# 1_uC.net
KiCad netlist of a schematic drawn in Altium Designer
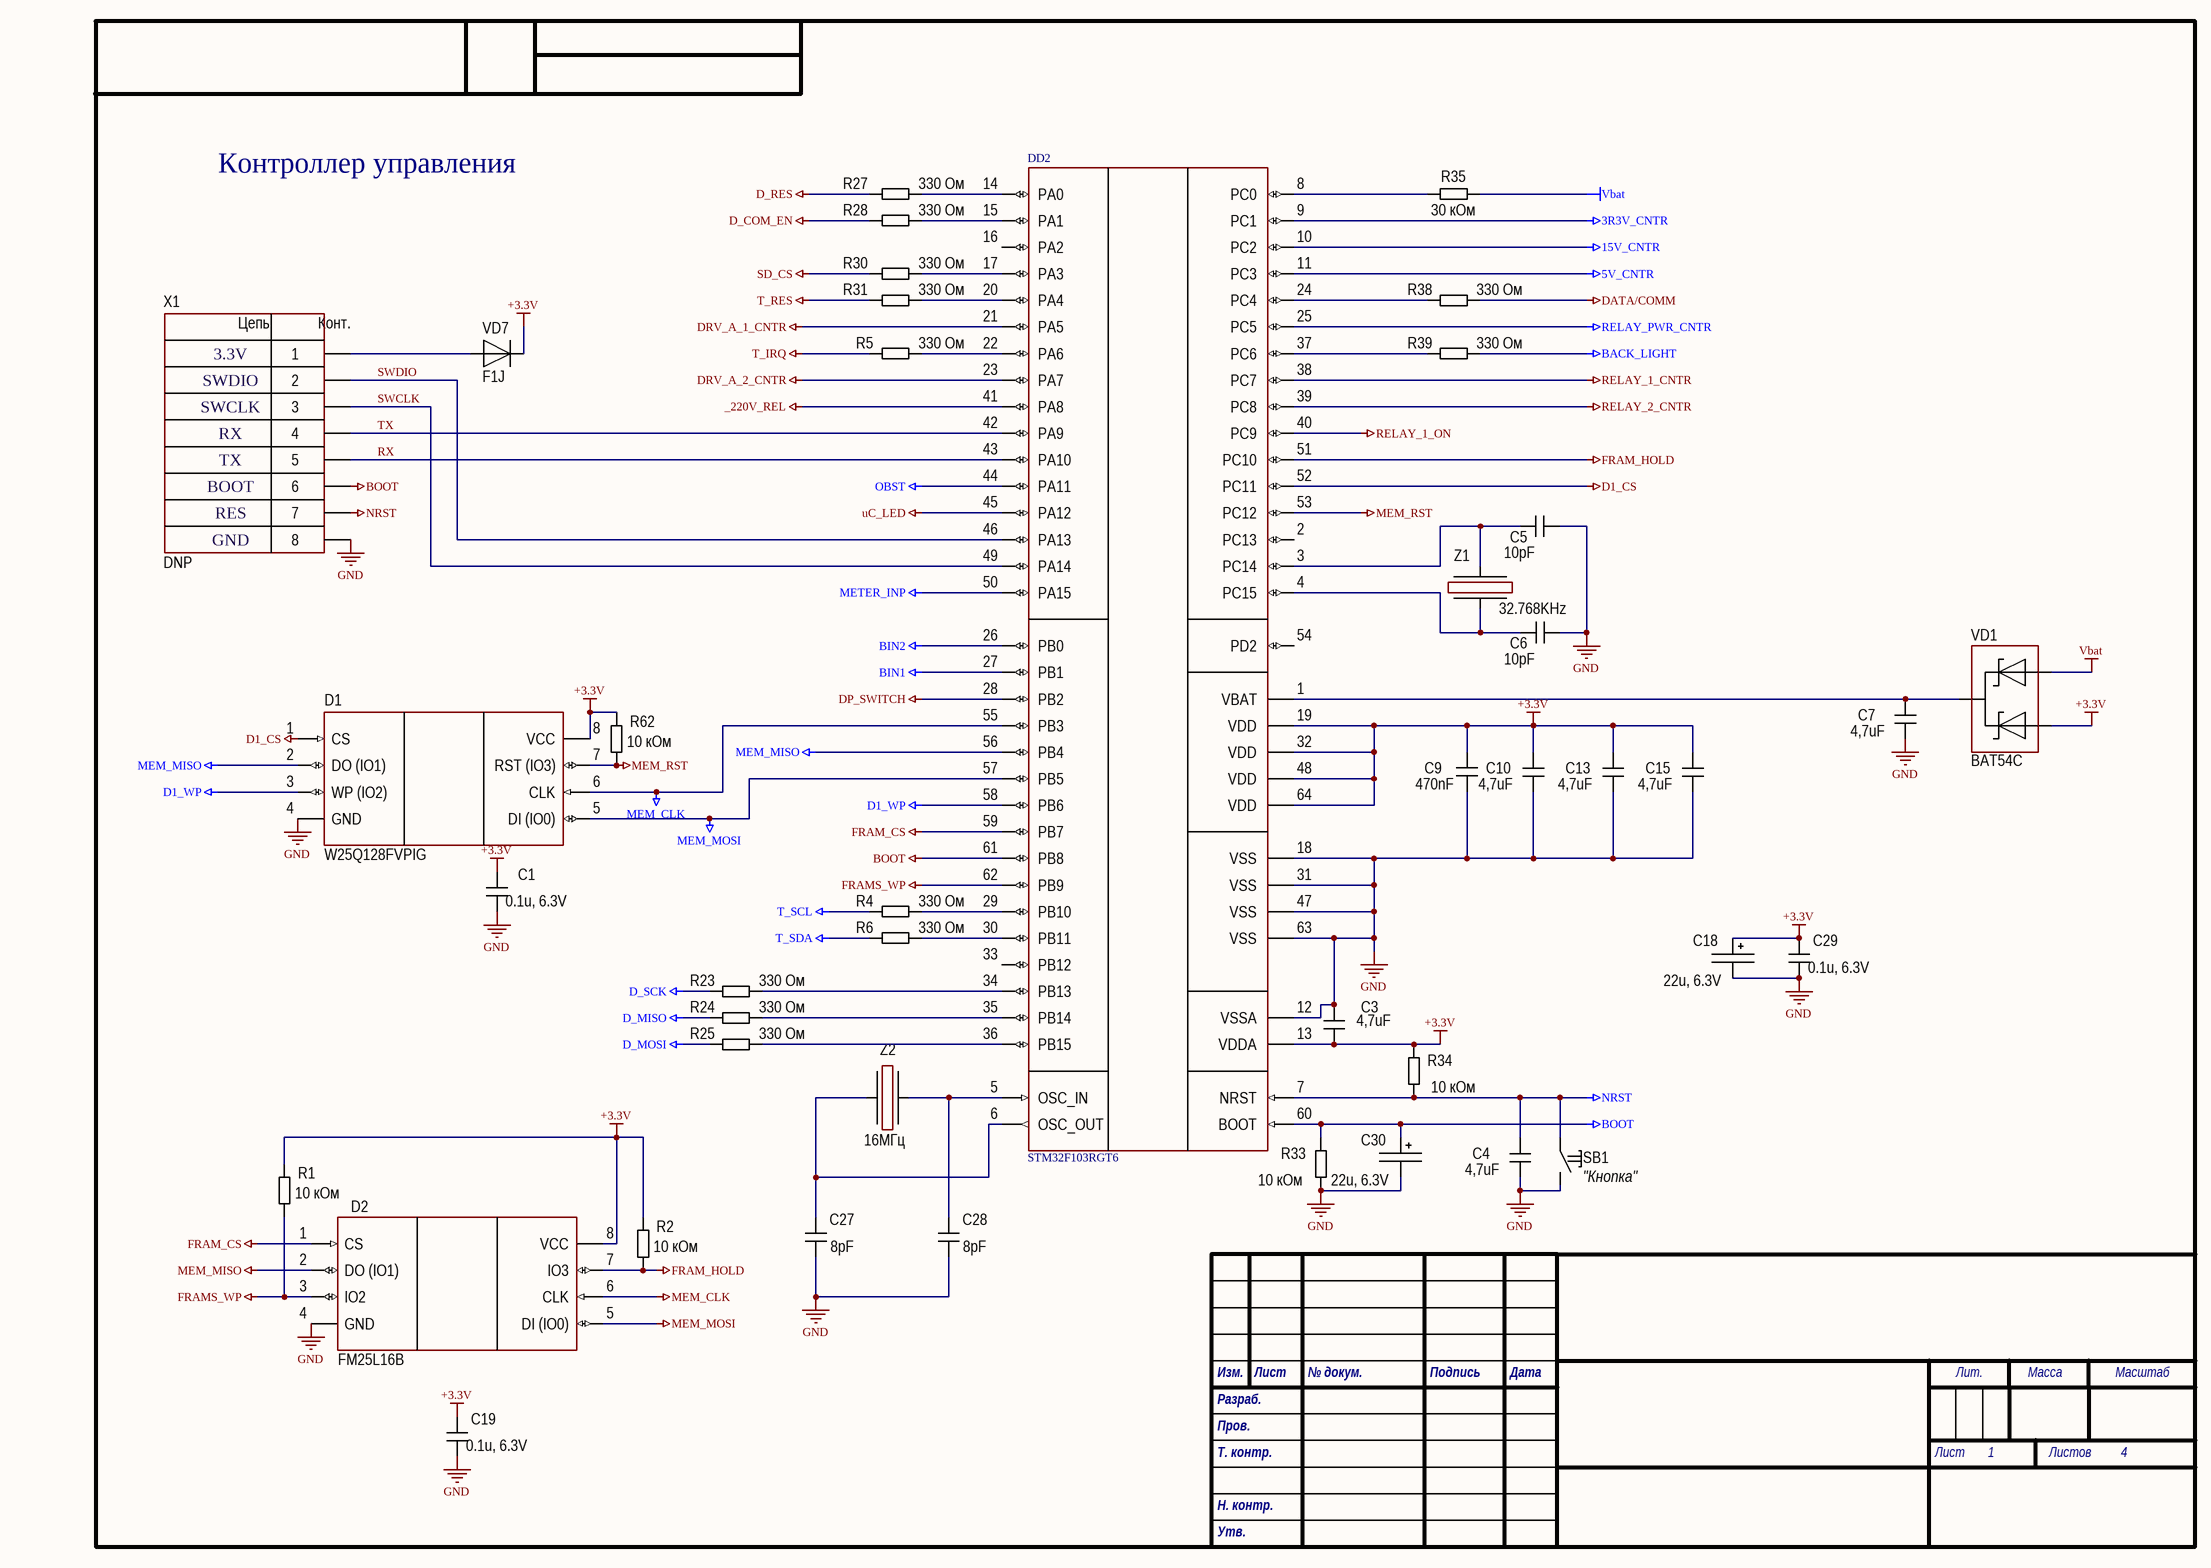
[diagram p0: 1_uC.SchDoc]

(export (version "E")
  (design (tool "Eeschema 10.0.6"))
  (components
    (comp (ref "C1")
      (value "0.1u, 6.3V")
      (footprint "CH0402C")
      (libsource (lib "Condensators") (part "Capacitor"))
    )
    (comp (ref "C3")
      (value "4,7uF")
      (footprint "CH0402C")
      (description "0402")
      (libsource (lib "Condensators") (part "Capacitor"))
    )
    (comp (ref "C4")
      (value "4,7uF")
      (footprint "CH0402C")
      (description "0402")
      (libsource (lib "Condensators") (part "Capacitor"))
    )
    (comp (ref "C5")
      (value "10pF")
      (footprint "CH0402C")
      (description "0402")
      (libsource (lib "Condensators") (part "Capacitor"))
    )
    (comp (ref "C6")
      (value "10pF")
      (footprint "CH0402C")
      (description "0402")
      (libsource (lib "Condensators") (part "Capacitor"))
    )
    (comp (ref "C7")
      (value "4,7uF")
      (footprint "CH0402C")
      (description "0402")
      (libsource (lib "Condensators") (part "Capacitor"))
    )
    (comp (ref "C9")
      (value "470nF")
      (footprint "CH0402C")
      (description "0402")
      (libsource (lib "Condensators") (part "Capacitor"))
    )
    (comp (ref "C10")
      (value "4,7uF")
      (footprint "CH0402C")
      (description "0402")
      (libsource (lib "Condensators") (part "Capacitor"))
    )
    (comp (ref "C13")
      (value "4,7uF")
      (footprint "CH0402C")
      (description "0402")
      (libsource (lib "Condensators") (part "Capacitor"))
    )
    (comp (ref "C15")
      (value "4,7uF")
      (footprint "CH0402C")
      (description "0402")
      (libsource (lib "Condensators") (part "Capacitor"))
    )
    (comp (ref "C18")
      (value "22u, 6.3V")
      (footprint "TANTAL_A")
      (libsource (lib "Condensators") (part "TantalCap"))
    )
    (comp (ref "C19")
      (value "0.1u, 6.3V")
      (footprint "CH0402C")
      (libsource (lib "Condensators") (part "Capacitor"))
    )
    (comp (ref "C27")
      (value "8pF")
      (footprint "CH0402C")
      (description "0402")
      (libsource (lib "Condensators") (part "Capacitor"))
    )
    (comp (ref "C28")
      (value "8pF")
      (footprint "CH0402C")
      (description "0402")
      (libsource (lib "Condensators") (part "Capacitor"))
    )
    (comp (ref "C29")
      (value "0.1u, 6.3V")
      (footprint "CH0402C")
      (libsource (lib "Condensators") (part "Capacitor"))
    )
    (comp (ref "C30")
      (value "22u, 6.3V")
      (footprint "TANTAL_A")
      (libsource (lib "Condensators") (part "TantalCap"))
    )
    (comp (ref "D1")
      (value "W25Q128FVPIG")
      (footprint "8-WSON (5x6mm)without_holes")
      (description "Flash")
      (fields (field (name "MANUFACTURER") "Winbond Electronics"))
      (libsource (lib "MicroIC") (part "W25Q128FVPIG"))
    )
    (comp (ref "D2")
      (value "FM25L16B")
      (footprint "8-SOIC")
      (description "Flash")
      (fields (field (name "MANUFACTURER") "Winbond Electronics"))
      (libsource (lib "MicroIC") (part "W25Q80JVSSIQ"))
    )
    (comp (ref "DD2")
      (value "STM32F103RGT6")
      (footprint "64-LQFP")
      (description "Cortex-M3 (64-LQFP)")
      (libsource (lib "MicroIC") (part "STM32F103RCT6"))
    )
    (comp (ref "R1")
      (value "10 кОм")
      (footprint "CH0402R")
      (description "0603")
      (libsource (lib "Resistors") (part "Resistor"))
    )
    (comp (ref "R2")
      (value "10 кОм")
      (footprint "CH0402R")
      (description "0603")
      (libsource (lib "Resistors") (part "Resistor"))
    )
    (comp (ref "R4")
      (value "330 Ом")
      (footprint "CH0402R")
      (description "0603")
      (libsource (lib "Resistors") (part "Resistor"))
    )
    (comp (ref "R5")
      (value "330 Ом")
      (footprint "CH0402R")
      (description "0603")
      (libsource (lib "Resistors") (part "Resistor"))
    )
    (comp (ref "R6")
      (value "330 Ом")
      (footprint "CH0402R")
      (description "0603")
      (libsource (lib "Resistors") (part "Resistor"))
    )
    (comp (ref "R23")
      (value "330 Ом")
      (footprint "CH0402R")
      (description "0603")
      (libsource (lib "Resistors") (part "Resistor"))
    )
    (comp (ref "R24")
      (value "330 Ом")
      (footprint "CH0402R")
      (description "0603")
      (libsource (lib "Resistors") (part "Resistor"))
    )
    (comp (ref "R25")
      (value "330 Ом")
      (footprint "CH0402R")
      (description "0603")
      (libsource (lib "Resistors") (part "Resistor"))
    )
    (comp (ref "R27")
      (value "330 Ом")
      (footprint "CH0402R")
      (description "0603")
      (libsource (lib "Resistors") (part "Resistor"))
    )
    (comp (ref "R28")
      (value "330 Ом")
      (footprint "CH0402R")
      (description "0603")
      (libsource (lib "Resistors") (part "Resistor"))
    )
    (comp (ref "R30")
      (value "330 Ом")
      (footprint "CH0402R")
      (description "0603")
      (libsource (lib "Resistors") (part "Resistor"))
    )
    (comp (ref "R31")
      (value "330 Ом")
      (footprint "CH0402R")
      (description "0603")
      (libsource (lib "Resistors") (part "Resistor"))
    )
    (comp (ref "R33")
      (value "10 кОм")
      (footprint "CH0402R")
      (description "0805")
      (libsource (lib "Resistors") (part "Resistor"))
    )
    (comp (ref "R34")
      (value "10 кОм")
      (footprint "CH0402R")
      (description "0805")
      (libsource (lib "Resistors") (part "Resistor"))
    )
    (comp (ref "R35")
      (value "30 кОм")
      (footprint "CH0402R")
      (description "0603")
      (libsource (lib "Resistors") (part "Resistor"))
    )
    (comp (ref "R38")
      (value "330 Ом")
      (footprint "CH0402R")
      (description "0603")
      (libsource (lib "Resistors") (part "Resistor"))
    )
    (comp (ref "R39")
      (value "330 Ом")
      (footprint "CH0402R")
      (description "0603")
      (libsource (lib "Resistors") (part "Resistor"))
    )
    (comp (ref "R62")
      (value "10 кОм")
      (footprint "CH0402R")
      (description "0603")
      (libsource (lib "Resistors") (part "Resistor"))
    )
    (comp (ref "SB1")
      (value "\"Кнопка\"")
      (footprint "TL1014BF160QG")
      (description "6x6 mm")
      (libsource (lib "Connectors") (part "Tactile switches"))
    )
    (comp (ref "VD1")
      (value "BAT54C")
      (footprint "SOT23_123")
      (description "SOT-23")
      (libsource (lib "Diods") (part "Diod Schottky Array v.1"))
    )
    (comp (ref "VD7") (value "F1J") (footprint "SOD123F") (libsource (lib "Diods") (part "Diod")))
    (comp (ref "X1")
      (value "DNP")
      (footprint "CON: PBS-8")
      (description "Pin header 8")
      (libsource (lib "Connectors") (part "8-Connector"))
    )
    (comp (ref "Z1")
      (value "32.768KHz")
      (footprint "OSC: 3215")
      (libsource (lib "Melochi") (part "Oscillator"))
    )
    (comp (ref "Z2")
      (value "16МГц")
      (footprint "OSC: ABM3")
      (description "NX5032GA-16.000000MHZ-LN-CD-1")
      (libsource (lib "") (part "Oscillator_1"))
    )
  )
  (nets
    (net (code "1") (name "+3.3V") (class "Default")
      (node (ref "C1") (pin "2") (pinfunction "2_2") (pintype "passive"))
      (node (ref "C10") (pin "2") (pinfunction "2_2") (pintype "passive"))
      (node (ref "C13") (pin "2") (pinfunction "2_2") (pintype "passive"))
      (node (ref "C15") (pin "2") (pinfunction "2_2") (pintype "passive"))
      (node (ref "C18") (pin "1") (pinfunction "1_1") (pintype "power_in"))
      (node (ref "C19") (pin "2") (pinfunction "2_2") (pintype "passive"))
      (node (ref "C29") (pin "2") (pinfunction "2_2") (pintype "passive"))
      (node (ref "C3") (pin "1") (pinfunction "1_1") (pintype "passive"))
      (node (ref "C9") (pin "1") (pinfunction "1_1") (pintype "passive"))
      (node (ref "D1") (pin "8") (pinfunction "VCC_8") (pintype "power_in"))
      (node (ref "D2") (pin "8") (pinfunction "VCC_8") (pintype "power_in"))
      (node (ref "DD2") (pin "13") (pinfunction "VDDA_13") (pintype "power_in"))
      (node (ref "DD2") (pin "19") (pinfunction "VDD_19") (pintype "power_in"))
      (node (ref "DD2") (pin "32") (pinfunction "VDD_32") (pintype "power_in"))
      (node (ref "DD2") (pin "48") (pinfunction "VDD_48") (pintype "power_in"))
      (node (ref "DD2") (pin "64") (pinfunction "VDD_64") (pintype "power_in"))
      (node (ref "R1") (pin "2") (pinfunction "2_2") (pintype "passive"))
      (node (ref "R2") (pin "2") (pinfunction "2_2") (pintype "passive"))
      (node (ref "R34") (pin "2") (pinfunction "2_2") (pintype "passive"))
      (node (ref "R62") (pin "2") (pinfunction "2_2") (pintype "passive"))
      (node (ref "VD1") (pin "3") (pinfunction "3_3") (pintype "passive"))
      (node (ref "VD7") (pin "2") (pinfunction "2_2") (pintype "passive"))
    )
    (net (code "2") (name "/RX") (class "Default")
      (node (ref "DD2") (pin "43") (pinfunction "PA10_43") (pintype "bidirectional"))
      (node (ref "X1") (pin "5") (pinfunction "5_5") (pintype "power_in"))
    )
    (net (code "3") (name "/SWCLK") (class "Default")
      (node (ref "DD2") (pin "49") (pinfunction "PA14_49") (pintype "bidirectional"))
      (node (ref "X1") (pin "3") (pinfunction "3_3") (pintype "power_in"))
    )
    (net (code "4") (name "/SWDIO") (class "Default")
      (node (ref "DD2") (pin "46") (pinfunction "PA13_46") (pintype "bidirectional"))
      (node (ref "X1") (pin "2") (pinfunction "2_2") (pintype "passive"))
    )
    (net (code "5") (name "/TX") (class "Default")
      (node (ref "DD2") (pin "42") (pinfunction "PA9_42") (pintype "bidirectional"))
      (node (ref "X1") (pin "4") (pinfunction "4_4") (pintype "power_in"))
    )
    (net (code "6") (name "3R3V_CNTR") (class "Default")
      (node (ref "DD2") (pin "9") (pinfunction "PC1_9") (pintype "bidirectional"))
    )
    (net (code "7") (name "5V_CNTR") (class "Default")
      (node (ref "DD2") (pin "11") (pinfunction "PC3_11") (pintype "bidirectional"))
    )
    (net (code "8") (name "15V_CNTR") (class "Default")
      (node (ref "DD2") (pin "10") (pinfunction "PC2_10") (pintype "bidirectional"))
    )
    (net (code "9") (name "BACK_LIGHT") (class "Default")
      (node (ref "R39") (pin "1") (pinfunction "1_1") (pintype "passive"))
    )
    (net (code "10") (name "BIN1") (class "Default")
      (node (ref "DD2") (pin "27") (pinfunction "PB1_27") (pintype "bidirectional"))
    )
    (net (code "11") (name "BIN2") (class "Default")
      (node (ref "DD2") (pin "26") (pinfunction "PB0_26") (pintype "bidirectional"))
    )
    (net (code "12") (name "BOOT") (class "Default")
      (node (ref "C30") (pin "1") (pinfunction "1_1") (pintype "power_in"))
      (node (ref "DD2") (pin "60") (pinfunction "BOOT_60") (pintype "input"))
      (node (ref "DD2") (pin "61") (pinfunction "PB8_61") (pintype "bidirectional"))
      (node (ref "R33") (pin "2") (pinfunction "2_2") (pintype "passive"))
      (node (ref "X1") (pin "6") (pinfunction "6_6") (pintype "power_in"))
    )
    (net (code "13") (name "D1_CS") (class "Default")
      (node (ref "D1") (pin "1") (pinfunction "CS_1") (pintype "input"))
      (node (ref "DD2") (pin "52") (pinfunction "PC11_52") (pintype "bidirectional"))
    )
    (net (code "14") (name "D1_WP") (class "Default")
      (node (ref "D1") (pin "3") (pinfunction "WP_(IO2)_3") (pintype "bidirectional"))
      (node (ref "DD2") (pin "58") (pinfunction "PB6_58") (pintype "bidirectional"))
    )
    (net (code "15") (name "DATA{slash}COMM") (class "Default")
      (node (ref "R38") (pin "1") (pinfunction "1_1") (pintype "passive"))
    )
    (net (code "16") (name "DP_SWITCH") (class "Default")
      (node (ref "DD2") (pin "28") (pinfunction "PB2_28") (pintype "bidirectional"))
    )
    (net (code "17") (name "DRV_A_1_CNTR") (class "Default")
      (node (ref "DD2") (pin "21") (pinfunction "PA5_21") (pintype "bidirectional"))
    )
    (net (code "18") (name "DRV_A_2_CNTR") (class "Default")
      (node (ref "DD2") (pin "23") (pinfunction "PA7_23") (pintype "bidirectional"))
    )
    (net (code "19") (name "D_COM_EN") (class "Default")
      (node (ref "R28") (pin "1") (pinfunction "1_1") (pintype "passive"))
    )
    (net (code "20") (name "D_MISO") (class "Default")
      (node (ref "R24") (pin "1") (pinfunction "1_1") (pintype "passive"))
    )
    (net (code "21") (name "D_MOSI") (class "Default")
      (node (ref "R25") (pin "1") (pinfunction "1_1") (pintype "passive"))
    )
    (net (code "22") (name "D_RES") (class "Default")
      (node (ref "R27") (pin "1") (pinfunction "1_1") (pintype "passive"))
    )
    (net (code "23") (name "D_SCK") (class "Default")
      (node (ref "R23") (pin "1") (pinfunction "1_1") (pintype "passive"))
    )
    (net (code "24") (name "FRAMS_WP") (class "Default")
      (node (ref "D2") (pin "3") (pinfunction "IO2_3") (pintype "bidirectional"))
      (node (ref "DD2") (pin "62") (pinfunction "PB9_62") (pintype "bidirectional"))
      (node (ref "R1") (pin "1") (pinfunction "1_1") (pintype "passive"))
    )
    (net (code "25") (name "FRAM_CS") (class "Default")
      (node (ref "D2") (pin "1") (pinfunction "CS_1") (pintype "input"))
      (node (ref "DD2") (pin "59") (pinfunction "PB7_59") (pintype "bidirectional"))
    )
    (net (code "26") (name "FRAM_HOLD") (class "Default")
      (node (ref "D2") (pin "7") (pinfunction "IO3_7") (pintype "bidirectional"))
      (node (ref "DD2") (pin "51") (pinfunction "PC10_51") (pintype "bidirectional"))
      (node (ref "R2") (pin "1") (pinfunction "1_1") (pintype "passive"))
    )
    (net (code "27") (name "GND") (class "Default")
      (node (ref "C1") (pin "1") (pinfunction "1_1") (pintype "passive"))
      (node (ref "C10") (pin "1") (pinfunction "1_1") (pintype "passive"))
      (node (ref "C13") (pin "1") (pinfunction "1_1") (pintype "passive"))
      (node (ref "C15") (pin "1") (pinfunction "1_1") (pintype "passive"))
      (node (ref "C18") (pin "2") (pinfunction "2_2") (pintype "power_in"))
      (node (ref "C19") (pin "1") (pinfunction "1_1") (pintype "passive"))
      (node (ref "C27") (pin "1") (pinfunction "1_1") (pintype "passive"))
      (node (ref "C28") (pin "1") (pinfunction "1_1") (pintype "passive"))
      (node (ref "C29") (pin "1") (pinfunction "1_1") (pintype "passive"))
      (node (ref "C3") (pin "2") (pinfunction "2_2") (pintype "passive"))
      (node (ref "C30") (pin "2") (pinfunction "2_2") (pintype "power_in"))
      (node (ref "C4") (pin "1") (pinfunction "1_1") (pintype "passive"))
      (node (ref "C5") (pin "2") (pinfunction "2_2") (pintype "passive"))
      (node (ref "C6") (pin "1") (pinfunction "1_1") (pintype "passive"))
      (node (ref "C7") (pin "1") (pinfunction "1_1") (pintype "passive"))
      (node (ref "C9") (pin "2") (pinfunction "2_2") (pintype "passive"))
      (node (ref "D1") (pin "4") (pinfunction "GND_4") (pintype "power_in"))
      (node (ref "D2") (pin "4") (pinfunction "GND_4") (pintype "power_in"))
      (node (ref "DD2") (pin "12") (pinfunction "VSSA_12") (pintype "power_in"))
      (node (ref "DD2") (pin "18") (pinfunction "VSS_18") (pintype "power_in"))
      (node (ref "DD2") (pin "31") (pinfunction "VSS_31") (pintype "power_in"))
      (node (ref "DD2") (pin "47") (pinfunction "VSS_47") (pintype "power_in"))
      (node (ref "DD2") (pin "63") (pinfunction "VSS_63") (pintype "power_in"))
      (node (ref "R33") (pin "1") (pinfunction "1_1") (pintype "passive"))
      (node (ref "SB1") (pin "2") (pinfunction "2_2") (pintype "passive"))
      (node (ref "X1") (pin "8") (pinfunction "8_8") (pintype "power_in"))
    )
    (net (code "28") (name "MEM_CLK") (class "Default")
      (node (ref "D1") (pin "6") (pinfunction "CLK_6") (pintype "input"))
      (node (ref "D2") (pin "6") (pinfunction "CLK_6") (pintype "input"))
      (node (ref "DD2") (pin "55") (pinfunction "PB3_55") (pintype "bidirectional"))
    )
    (net (code "29") (name "MEM_MISO") (class "Default")
      (node (ref "D1") (pin "2") (pinfunction "DO_(IO1)_2") (pintype "bidirectional"))
      (node (ref "D2") (pin "2") (pinfunction "DO_(IO1)_2") (pintype "bidirectional"))
      (node (ref "DD2") (pin "56") (pinfunction "PB4_56") (pintype "bidirectional"))
    )
    (net (code "30") (name "MEM_MOSI") (class "Default")
      (node (ref "D1") (pin "5") (pinfunction "DI_(IO0)_5") (pintype "bidirectional"))
      (node (ref "D2") (pin "5") (pinfunction "DI_(IO0)_5") (pintype "bidirectional"))
      (node (ref "DD2") (pin "57") (pinfunction "PB5_57") (pintype "bidirectional"))
    )
    (net (code "31") (name "MEM_RST") (class "Default")
      (node (ref "D1") (pin "7") (pinfunction "RST_(IO3)_7") (pintype "bidirectional"))
      (node (ref "DD2") (pin "53") (pinfunction "PC12_53") (pintype "bidirectional"))
      (node (ref "R62") (pin "1") (pinfunction "1_1") (pintype "passive"))
    )
    (net (code "32") (name "METER_INP") (class "Default")
      (node (ref "DD2") (pin "50") (pinfunction "PA15_50") (pintype "bidirectional"))
    )
    (net (code "33") (name "NRST") (class "Default")
      (node (ref "C4") (pin "2") (pinfunction "2_2") (pintype "passive"))
      (node (ref "DD2") (pin "7") (pinfunction "NRST_7") (pintype "input"))
      (node (ref "R34") (pin "1") (pinfunction "1_1") (pintype "passive"))
      (node (ref "SB1") (pin "1") (pinfunction "1_1") (pintype "passive"))
      (node (ref "X1") (pin "7") (pinfunction "7_7") (pintype "power_in"))
    )
    (net (code "34") (name "Net-(DD2-OSC_IN)") (class "Default")
      (node (ref "C28") (pin "2") (pinfunction "2_2") (pintype "passive"))
      (node (ref "DD2") (pin "5") (pinfunction "OSC_IN_5") (pintype "input"))
      (node (ref "Z2") (pin "3") (pinfunction "3_3") (pintype "passive"))
    )
    (net (code "35") (name "Net-(DD2-OSC_OUT)") (class "Default")
      (node (ref "C27") (pin "2") (pinfunction "2_2") (pintype "passive"))
      (node (ref "DD2") (pin "6") (pinfunction "OSC_OUT_6") (pintype "output"))
      (node (ref "Z2") (pin "1") (pinfunction "1_1") (pintype "passive"))
    )
    (net (code "36") (name "Net-(DD2-PA0)") (class "Default")
      (node (ref "DD2") (pin "14") (pinfunction "PA0_14") (pintype "bidirectional"))
      (node (ref "R27") (pin "2") (pinfunction "2_2") (pintype "passive"))
    )
    (net (code "37") (name "Net-(DD2-PA1)") (class "Default")
      (node (ref "DD2") (pin "15") (pinfunction "PA1_15") (pintype "bidirectional"))
      (node (ref "R28") (pin "2") (pinfunction "2_2") (pintype "passive"))
    )
    (net (code "38") (name "Net-(DD2-PA3)") (class "Default")
      (node (ref "DD2") (pin "17") (pinfunction "PA3_17") (pintype "bidirectional"))
      (node (ref "R30") (pin "2") (pinfunction "2_2") (pintype "passive"))
    )
    (net (code "39") (name "Net-(DD2-PA4)") (class "Default")
      (node (ref "DD2") (pin "20") (pinfunction "PA4_20") (pintype "bidirectional"))
      (node (ref "R31") (pin "2") (pinfunction "2_2") (pintype "passive"))
    )
    (net (code "40") (name "Net-(DD2-PA6)") (class "Default")
      (node (ref "DD2") (pin "22") (pinfunction "PA6_22") (pintype "bidirectional"))
      (node (ref "R5") (pin "2") (pinfunction "2_2") (pintype "passive"))
    )
    (net (code "41") (name "Net-(DD2-PB10)") (class "Default")
      (node (ref "DD2") (pin "29") (pinfunction "PB10_29") (pintype "bidirectional"))
      (node (ref "R4") (pin "2") (pinfunction "2_2") (pintype "passive"))
    )
    (net (code "42") (name "Net-(DD2-PB11)") (class "Default")
      (node (ref "DD2") (pin "30") (pinfunction "PB11_30") (pintype "bidirectional"))
      (node (ref "R6") (pin "2") (pinfunction "2_2") (pintype "passive"))
    )
    (net (code "43") (name "Net-(DD2-PB13)") (class "Default")
      (node (ref "DD2") (pin "34") (pinfunction "PB13_34") (pintype "bidirectional"))
      (node (ref "R23") (pin "2") (pinfunction "2_2") (pintype "passive"))
    )
    (net (code "44") (name "Net-(DD2-PB14)") (class "Default")
      (node (ref "DD2") (pin "35") (pinfunction "PB14_35") (pintype "bidirectional"))
      (node (ref "R24") (pin "2") (pinfunction "2_2") (pintype "passive"))
    )
    (net (code "45") (name "Net-(DD2-PB15)") (class "Default")
      (node (ref "DD2") (pin "36") (pinfunction "PB15_36") (pintype "bidirectional"))
      (node (ref "R25") (pin "2") (pinfunction "2_2") (pintype "passive"))
    )
    (net (code "46") (name "Net-(DD2-PC0)") (class "Default")
      (node (ref "DD2") (pin "8") (pinfunction "PC0_8") (pintype "bidirectional"))
      (node (ref "R35") (pin "2") (pinfunction "2_2") (pintype "passive"))
    )
    (net (code "47") (name "Net-(DD2-PC4)") (class "Default")
      (node (ref "DD2") (pin "24") (pinfunction "PC4_24") (pintype "bidirectional"))
      (node (ref "R38") (pin "2") (pinfunction "2_2") (pintype "passive"))
    )
    (net (code "48") (name "Net-(DD2-PC6)") (class "Default")
      (node (ref "DD2") (pin "37") (pinfunction "PC6_37") (pintype "bidirectional"))
      (node (ref "R39") (pin "2") (pinfunction "2_2") (pintype "passive"))
    )
    (net (code "49") (name "Net-(DD2-PC14)") (class "Default")
      (node (ref "C5") (pin "1") (pinfunction "1_1") (pintype "passive"))
      (node (ref "DD2") (pin "3") (pinfunction "PC14_3") (pintype "bidirectional"))
      (node (ref "Z1") (pin "3") (pinfunction "3_3") (pintype "passive"))
    )
    (net (code "50") (name "Net-(DD2-PC15)") (class "Default")
      (node (ref "C6") (pin "2") (pinfunction "2_2") (pintype "passive"))
      (node (ref "DD2") (pin "4") (pinfunction "PC15_4") (pintype "bidirectional"))
      (node (ref "Z1") (pin "1") (pinfunction "1_1") (pintype "passive"))
    )
    (net (code "51") (name "Net-(DD2-VBAT)") (class "Default")
      (node (ref "C7") (pin "2") (pinfunction "2_2") (pintype "passive"))
      (node (ref "DD2") (pin "1") (pinfunction "VBAT_1") (pintype "power_in"))
      (node (ref "VD1") (pin "2") (pinfunction "2_2") (pintype "passive"))
    )
    (net (code "52") (name "Net-(VD7-Pad1)") (class "Default")
      (node (ref "VD7") (pin "1") (pinfunction "1_1") (pintype "passive"))
      (node (ref "X1") (pin "1") (pinfunction "1_1") (pintype "passive"))
    )
    (net (code "53") (name "OBST") (class "Default")
      (node (ref "DD2") (pin "44") (pinfunction "PA11_44") (pintype "bidirectional"))
    )
    (net (code "54") (name "RELAY_1_CNTR") (class "Default")
      (node (ref "DD2") (pin "38") (pinfunction "PC7_38") (pintype "bidirectional"))
    )
    (net (code "55") (name "RELAY_1_ON") (class "Default")
      (node (ref "DD2") (pin "40") (pinfunction "PC9_40") (pintype "bidirectional"))
    )
    (net (code "56") (name "RELAY_2_CNTR") (class "Default")
      (node (ref "DD2") (pin "39") (pinfunction "PC8_39") (pintype "bidirectional"))
    )
    (net (code "57") (name "RELAY_PWR_CNTR") (class "Default")
      (node (ref "DD2") (pin "25") (pinfunction "PC5_25") (pintype "bidirectional"))
    )
    (net (code "58") (name "SD_CS") (class "Default")
      (node (ref "R30") (pin "1") (pinfunction "1_1") (pintype "passive"))
    )
    (net (code "59") (name "T_IRQ") (class "Default")
      (node (ref "R5") (pin "1") (pinfunction "1_1") (pintype "passive"))
    )
    (net (code "60") (name "T_RES") (class "Default")
      (node (ref "R31") (pin "1") (pinfunction "1_1") (pintype "passive"))
    )
    (net (code "61") (name "T_SCL") (class "Default")
      (node (ref "R4") (pin "1") (pinfunction "1_1") (pintype "passive"))
    )
    (net (code "62") (name "T_SDA") (class "Default")
      (node (ref "R6") (pin "1") (pinfunction "1_1") (pintype "passive"))
    )
    (net (code "63") (name "Vbat") (class "Default")
      (node (ref "R35") (pin "1") (pinfunction "1_1") (pintype "passive"))
      (node (ref "VD1") (pin "1") (pinfunction "1_1") (pintype "passive"))
    )
    (net (code "64") (name "_220V_REL") (class "Default")
      (node (ref "DD2") (pin "41") (pinfunction "PA8_41") (pintype "bidirectional"))
    )
    (net (code "65") (name "uC_LED") (class "Default")
      (node (ref "DD2") (pin "45") (pinfunction "PA12_45") (pintype "bidirectional"))
    )
    (net (code "66") (name "unconnected-(DD2-PA2-Pad16)") (class "Default")
      (node (ref "DD2") (pin "16") (pinfunction "PA2_16") (pintype "bidirectional"))
    )
    (net (code "67") (name "unconnected-(DD2-PB12-Pad33)") (class "Default")
      (node (ref "DD2") (pin "33") (pinfunction "PB12_33") (pintype "bidirectional"))
    )
    (net (code "68") (name "unconnected-(DD2-PC13-Pad2)") (class "Default")
      (node (ref "DD2") (pin "2") (pinfunction "PC13_2") (pintype "bidirectional"))
    )
    (net (code "69") (name "unconnected-(DD2-PD2-Pad54)") (class "Default")
      (node (ref "DD2") (pin "54") (pinfunction "PD2_54") (pintype "bidirectional"))
    )
  )
)
